# IO_V1_1.net
KiCad netlist of a schematic drawn in EAGLE
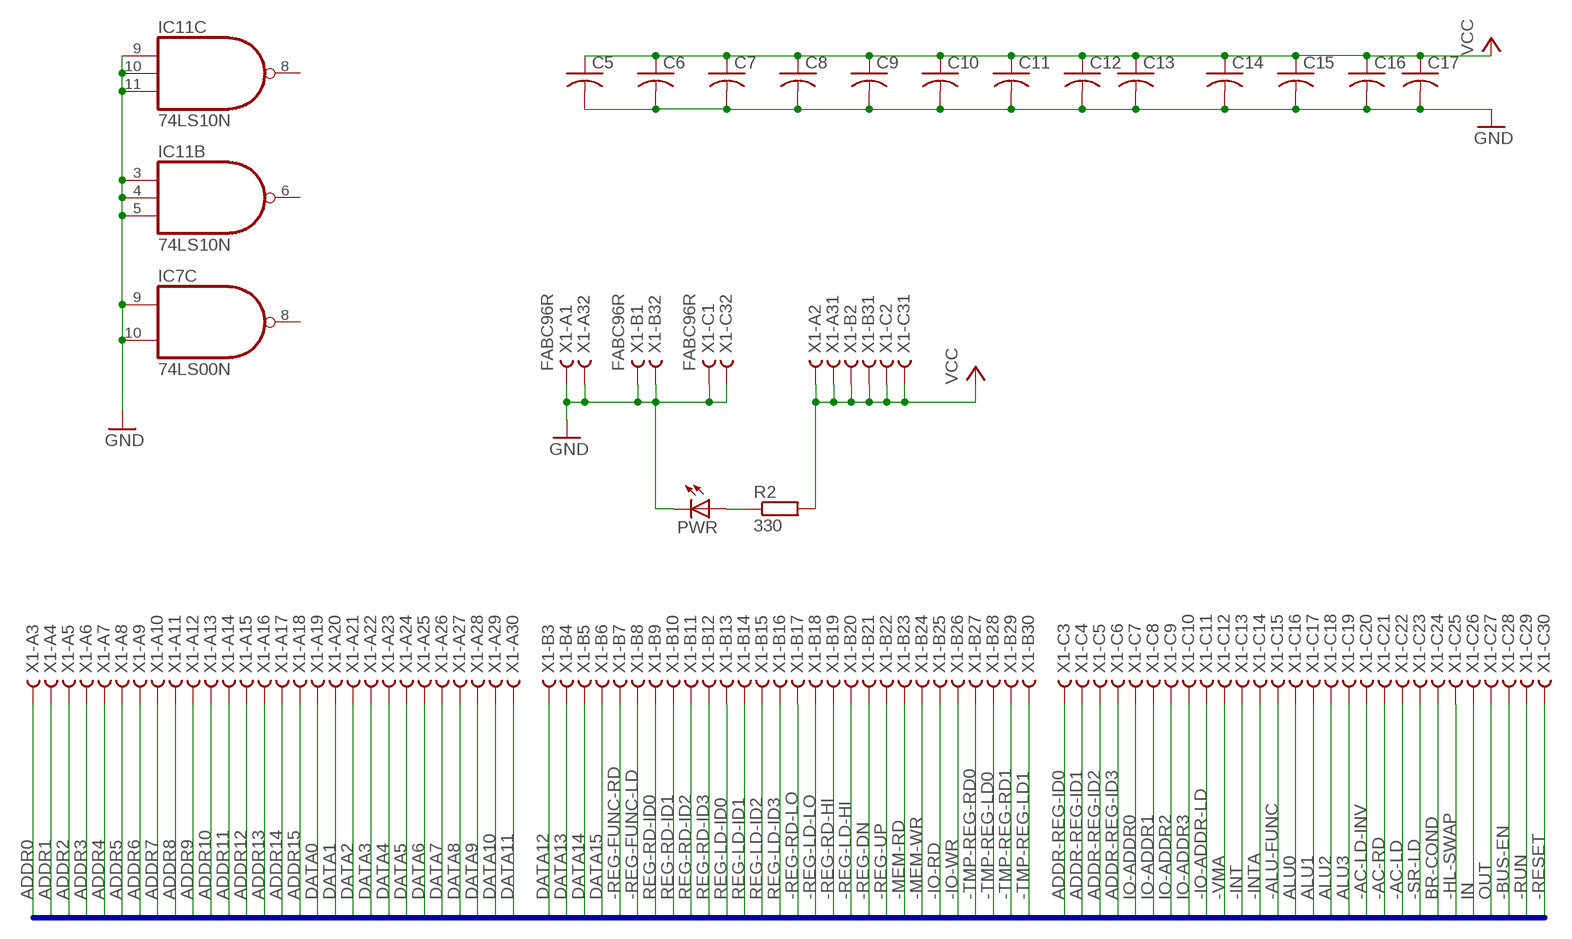
[diagram p0: schematic, sheet 1]
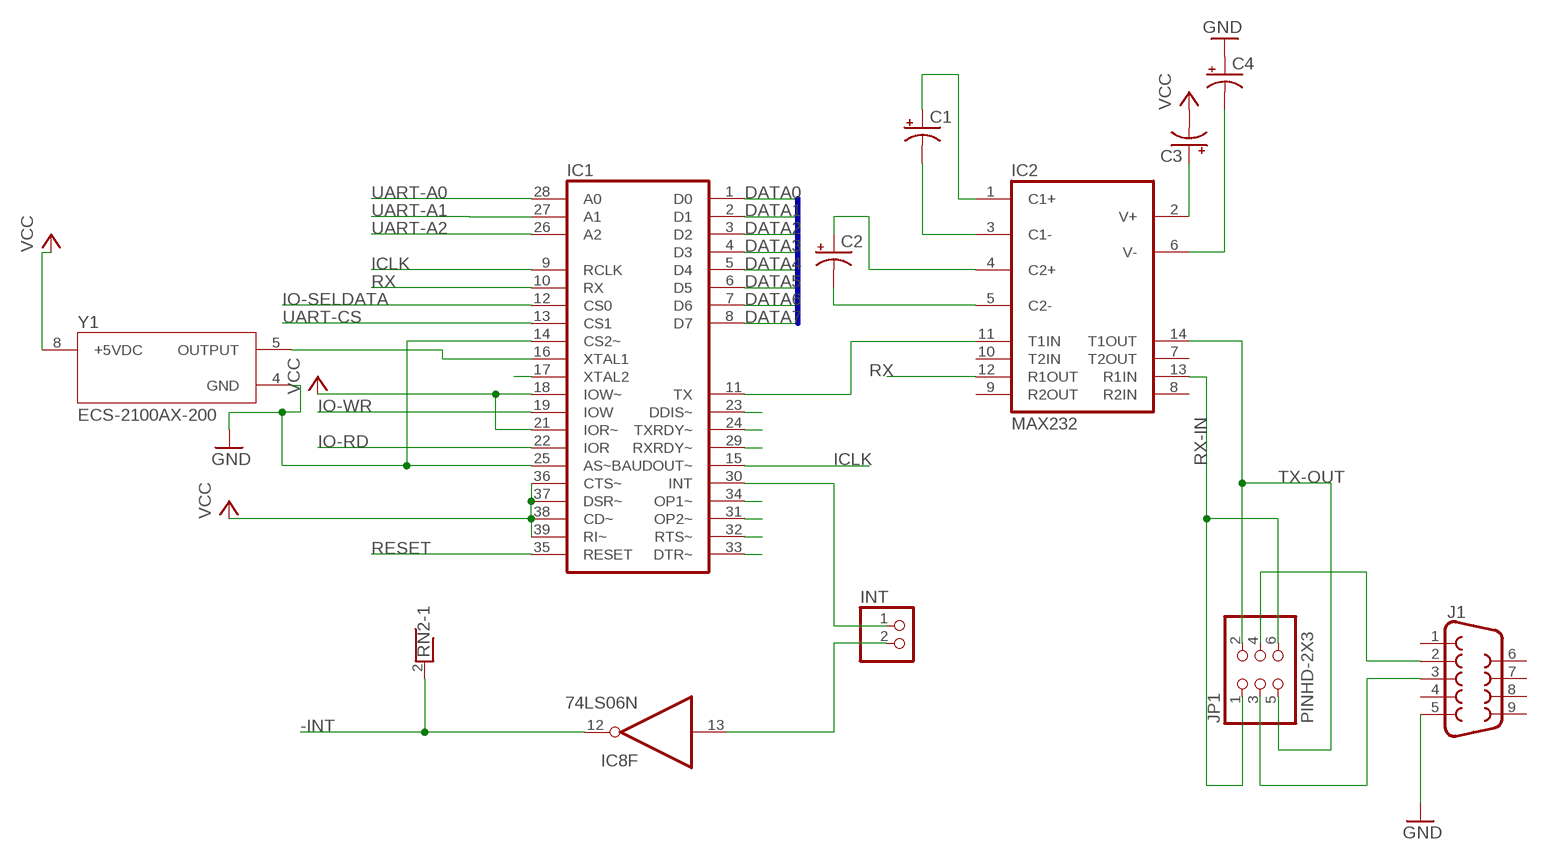
[diagram p1: schematic, sheet 2]
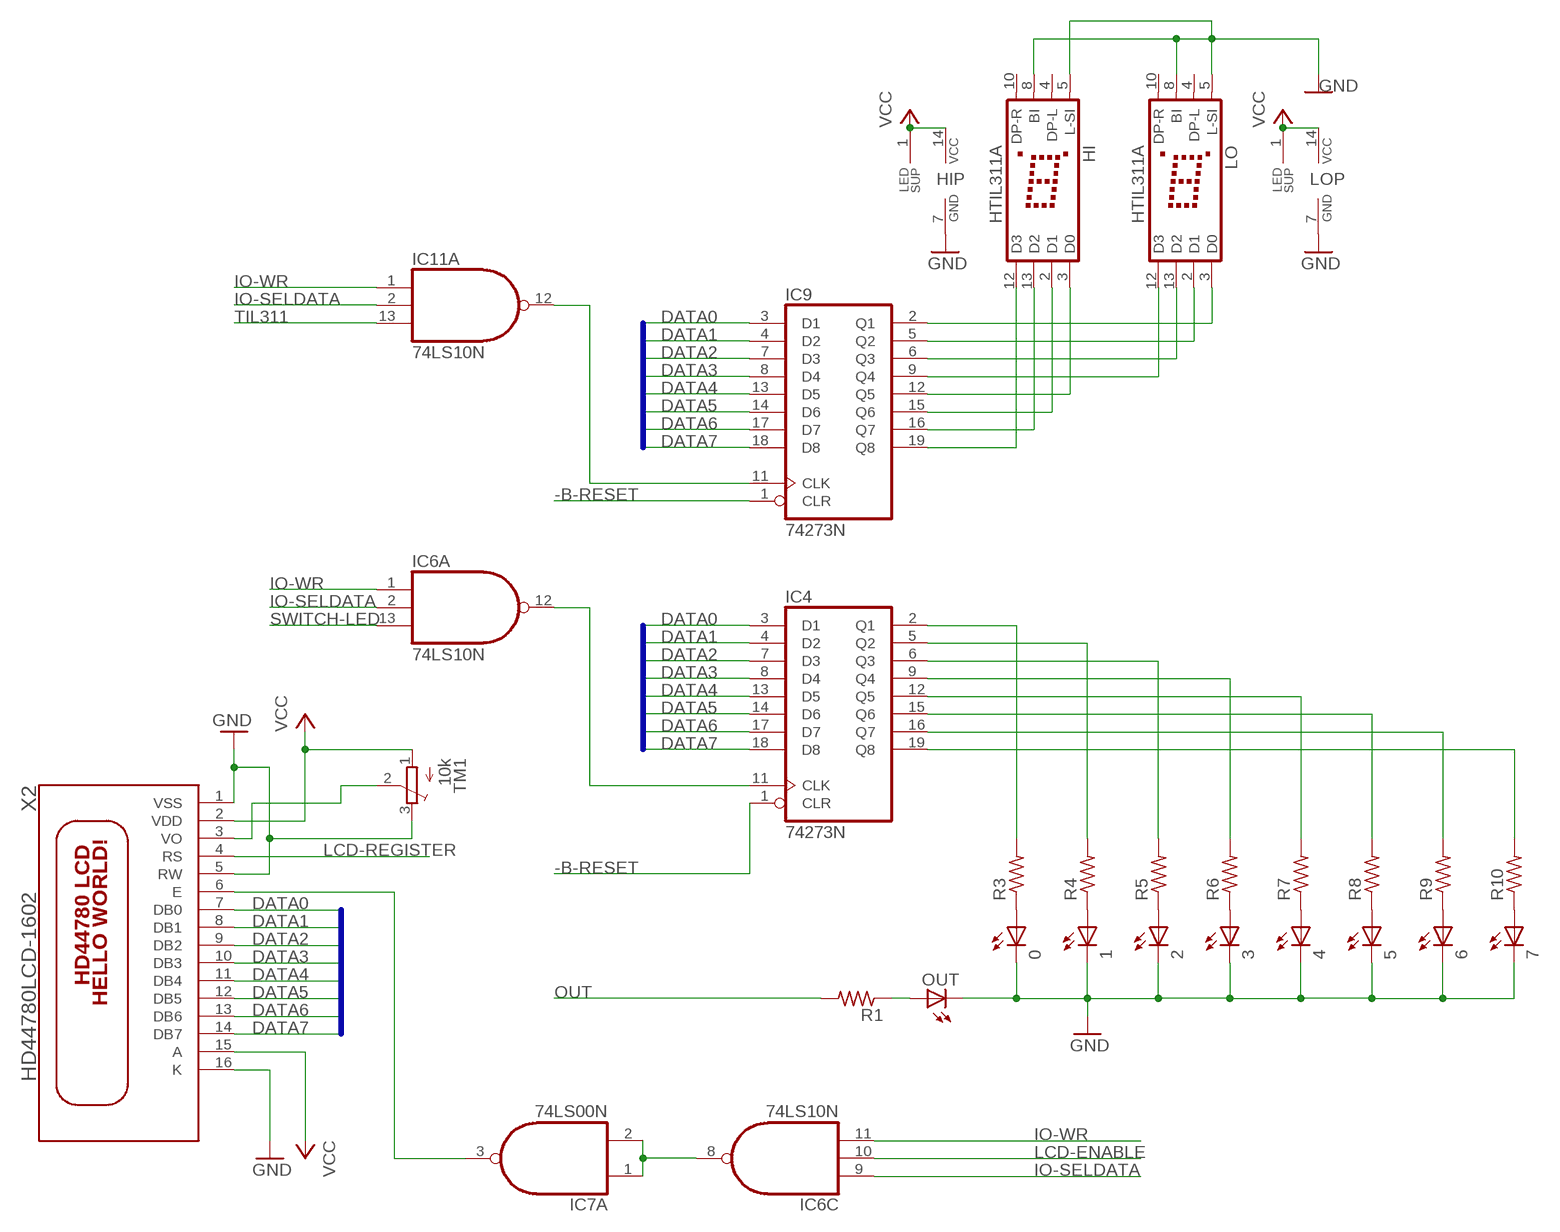
[diagram p2: schematic, sheet 3]
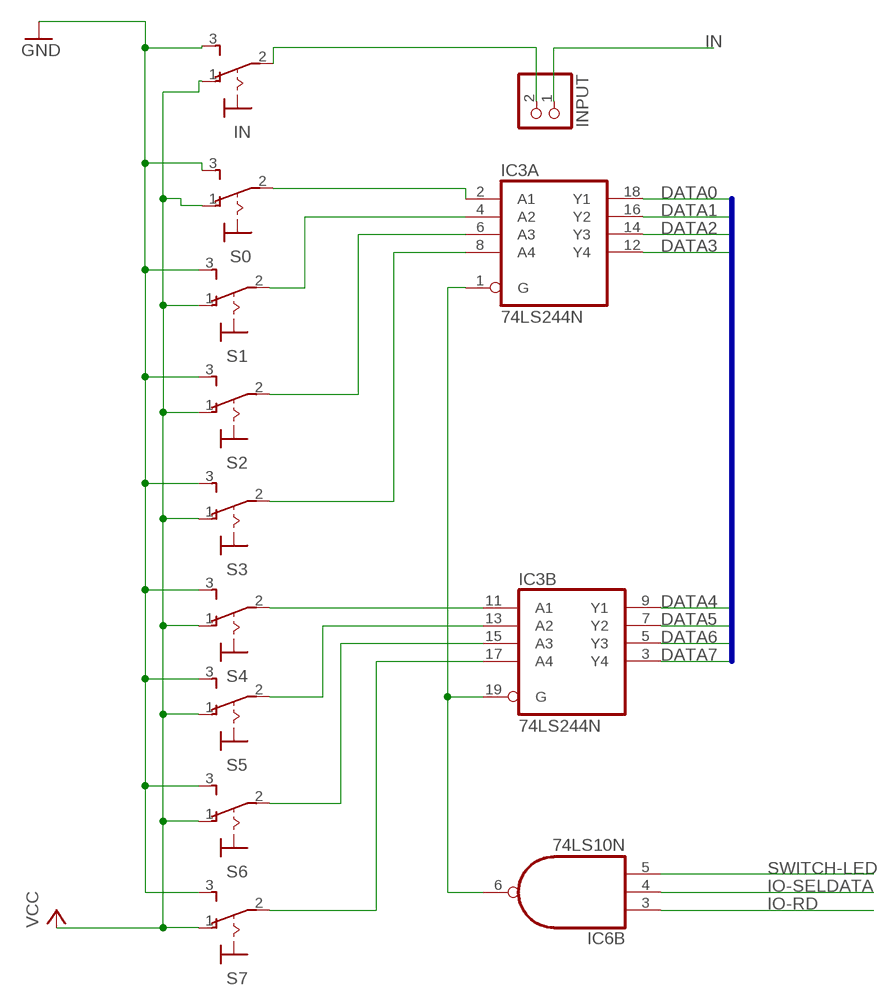
[diagram p3: schematic, sheet 4]
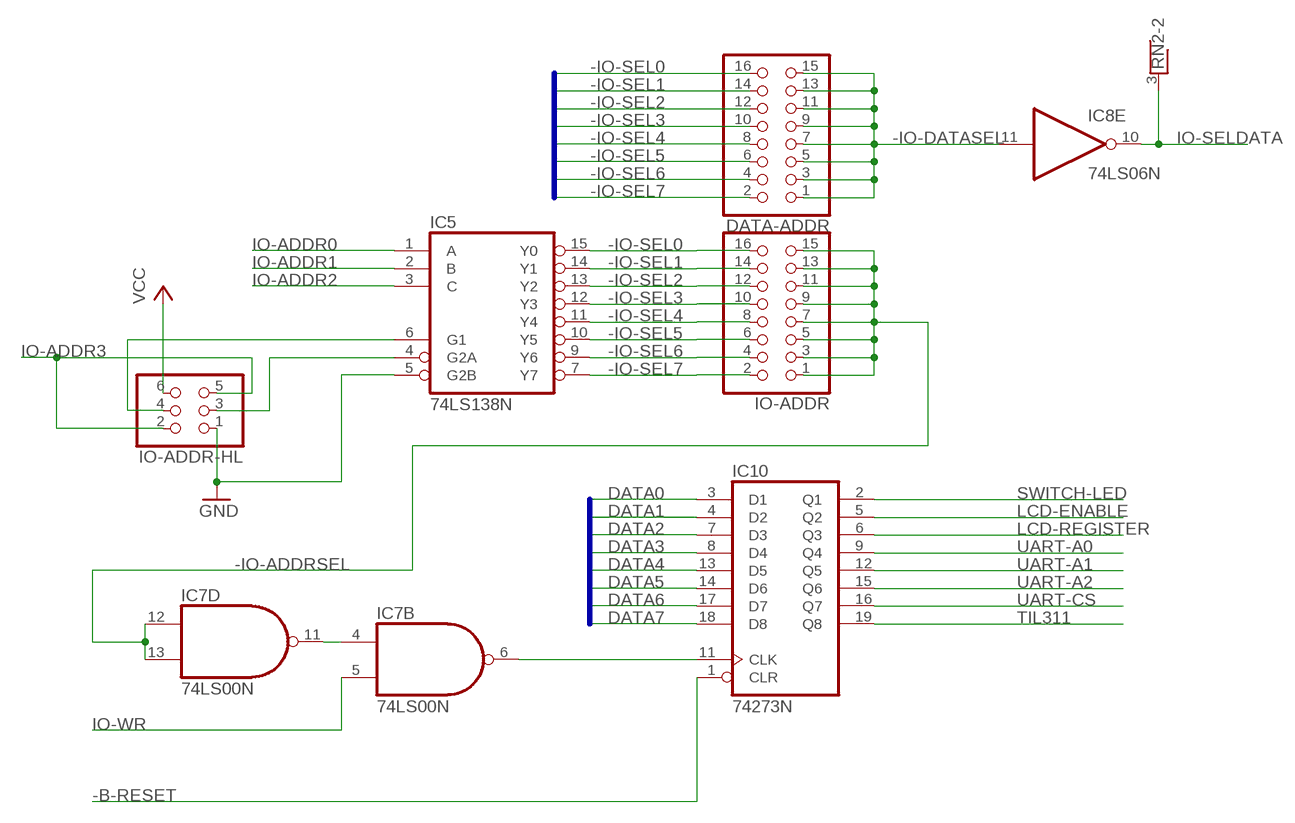
[diagram p4: schematic, sheet 5]
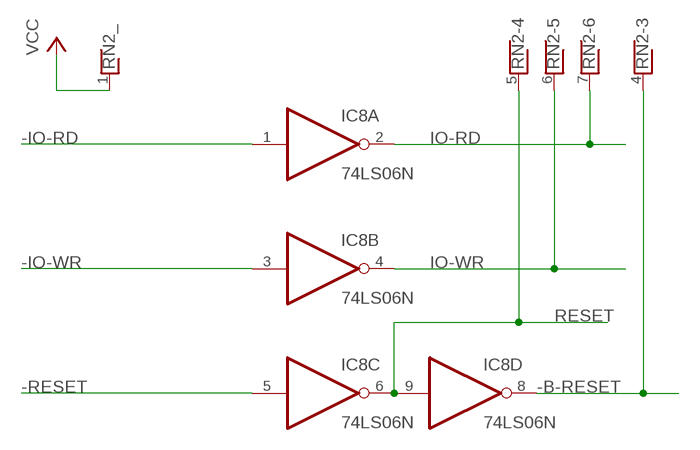
[diagram p5: schematic, sheet 6]

(export (version "E")
  (design (tool "Eeschema 10.0.6"))
  (components
    (comp (ref "DATA-ADDR")
      (value "PINHD-2X8")
      (footprint "eagle-import:2X08")
      (libsource (lib "eagle-import") (part "PINHD-2X8"))
    )
    (comp (ref "IC5")
      (value "74LS138N")
      (footprint "eagle-import:DIL16")
      (libsource (lib "eagle-import") (part "74138NLS"))
    )
    (comp (ref "IC7")
      (value "74LS00N")
      (footprint "eagle-import:DIL14")
      (libsource (lib "eagle-import") (part "7400NLS"))
    )
    (comp (ref "IC8")
      (value "74LS06N")
      (footprint "eagle-import:DIL14")
      (libsource (lib "eagle-import") (part "7406NLS"))
    )
    (comp (ref "IC10")
      (value "74273N")
      (footprint "eagle-import:DIL20")
      (libsource (lib "eagle-import") (part "74273N"))
    )
    (comp (ref "IO-ADDR")
      (value "PINHD-2X8")
      (footprint "eagle-import:2X08")
      (libsource (lib "eagle-import") (part "PINHD-2X8"))
    )
    (comp (ref "IO-ADDR-HL")
      (value "PINHD-2X3")
      (footprint "eagle-import:2X03")
      (libsource (lib "eagle-import") (part "pinhead_325_PINHD-2X3"))
    )
    (comp (ref "RN2")
      (value "RNX6")
      (footprint "eagle-import:RN-7")
      (libsource (lib "eagle-import") (part "RNX6"))
    )
    (comp (ref "C1")
      (value "CPOL-USE2,5-6E")
      (footprint "eagle-import:E2,5-6E")
      (libsource (lib "eagle-import") (part "CPOL-USE2,5-6E"))
    )
    (comp (ref "C2")
      (value "CPOL-USE2,5-6E")
      (footprint "eagle-import:E2,5-6E")
      (libsource (lib "eagle-import") (part "CPOL-USE2,5-6E"))
    )
    (comp (ref "C3")
      (value "CPOL-USE2,5-6E")
      (footprint "eagle-import:E2,5-6E")
      (libsource (lib "eagle-import") (part "CPOL-USE2,5-6E"))
    )
    (comp (ref "C4")
      (value "CPOL-USE2,5-6E")
      (footprint "eagle-import:E2,5-6E")
      (libsource (lib "eagle-import") (part "CPOL-USE2,5-6E"))
    )
    (comp (ref "IC1")
      (value "XR-16C550P")
      (footprint "eagle-import:DIL40")
      (fields (field (name "MPN") "ST16C450CP40"))
      (libsource (lib "eagle-import") (part "XR-16C550P"))
    )
    (comp (ref "IC2")
      (value "MAX232")
      (footprint "eagle-import:DIL16")
      (fields (field (name "MF") "MAXIM") (field (name "MPN") "MAX232ACPE+"))
      (libsource (lib "eagle-import") (part "MAX232"))
    )
    (comp (ref "INT")
      (value "PINHD-1X2")
      (footprint "eagle-import:1X02")
      (libsource (lib "eagle-import") (part "PINHD-1X2"))
    )
    (comp (ref "J1")
      (value "DB9FEMALE")
      (footprint "eagle-import:DB9")
      (libsource (lib "eagle-import") (part "DB9FEMALE"))
    )
    (comp (ref "JP1")
      (value "PINHD-2X3")
      (footprint "eagle-import:2X03")
      (libsource (lib "eagle-import") (part "PINHD-2X3"))
    )
    (comp (ref "Y1")
      (value "ECS-2100AX-200")
      (footprint "eagle-import:ECS-2100AX-200")
      (fields
        (field (name "DIGIKEY_PART_NUMBER") "X964-ND")
        (field (name "MANUFACTURER") "ECS Inc.")
        (field (name "CREATED_BY") "PCBLayout.com")
      )
      (libsource (lib "eagle-import") (part "ECS-2100AX-200"))
    )
    (comp (ref "0")
      (value "LED5MM")
      (footprint "eagle-import:LED5MM")
      (libsource (lib "eagle-import") (part "LED5MM"))
    )
    (comp (ref "1")
      (value "LED5MM")
      (footprint "eagle-import:LED5MM")
      (libsource (lib "eagle-import") (part "LED5MM"))
    )
    (comp (ref "2")
      (value "LED5MM")
      (footprint "eagle-import:LED5MM")
      (libsource (lib "eagle-import") (part "LED5MM"))
    )
    (comp (ref "3")
      (value "LED5MM")
      (footprint "eagle-import:LED5MM")
      (libsource (lib "eagle-import") (part "LED5MM"))
    )
    (comp (ref "4")
      (value "LED5MM")
      (footprint "eagle-import:LED5MM")
      (libsource (lib "eagle-import") (part "LED5MM"))
    )
    (comp (ref "5")
      (value "LED5MM")
      (footprint "eagle-import:LED5MM")
      (libsource (lib "eagle-import") (part "LED5MM"))
    )
    (comp (ref "6")
      (value "LED5MM")
      (footprint "eagle-import:LED5MM")
      (libsource (lib "eagle-import") (part "LED5MM"))
    )
    (comp (ref "7")
      (value "LED5MM")
      (footprint "eagle-import:LED5MM")
      (libsource (lib "eagle-import") (part "LED5MM"))
    )
    (comp (ref "HI")
      (value "HTIL311A")
      (footprint "eagle-import:HTIL311A")
      (libsource (lib "eagle-import") (part "HTIL311A"))
    )
    (comp (ref "IC4")
      (value "74273N")
      (footprint "eagle-import:DIL20")
      (libsource (lib "eagle-import") (part "74273N"))
    )
    (comp (ref "IC6")
      (value "74LS10N")
      (footprint "eagle-import:DIL14")
      (libsource (lib "eagle-import") (part "7410NLS"))
    )
    (comp (ref "IC9")
      (value "74273N")
      (footprint "eagle-import:DIL20")
      (libsource (lib "eagle-import") (part "74273N"))
    )
    (comp (ref "IC11")
      (value "74LS10N")
      (footprint "eagle-import:DIL14")
      (libsource (lib "eagle-import") (part "7410NLS"))
    )
    (comp (ref "LO")
      (value "HTIL311A")
      (footprint "eagle-import:HTIL311A")
      (libsource (lib "eagle-import") (part "HTIL311A"))
    )
    (comp (ref "OUT")
      (value "LED5MM")
      (footprint "eagle-import:LED5MM")
      (libsource (lib "eagle-import") (part "LED5MM"))
    )
    (comp (ref "R1")
      (value "R-US_0207/10")
      (footprint "eagle-import:0207_10")
      (libsource (lib "eagle-import") (part "R-US_0207/10"))
    )
    (comp (ref "R3")
      (value "R-US_0207/10")
      (footprint "eagle-import:0207_10")
      (libsource (lib "eagle-import") (part "R-US_0207/10"))
    )
    (comp (ref "R4")
      (value "R-US_0207/10")
      (footprint "eagle-import:0207_10")
      (libsource (lib "eagle-import") (part "R-US_0207/10"))
    )
    (comp (ref "R5")
      (value "R-US_0207/10")
      (footprint "eagle-import:0207_10")
      (libsource (lib "eagle-import") (part "R-US_0207/10"))
    )
    (comp (ref "R6")
      (value "R-US_0207/10")
      (footprint "eagle-import:0207_10")
      (libsource (lib "eagle-import") (part "R-US_0207/10"))
    )
    (comp (ref "R7")
      (value "R-US_0207/10")
      (footprint "eagle-import:0207_10")
      (libsource (lib "eagle-import") (part "R-US_0207/10"))
    )
    (comp (ref "R8")
      (value "R-US_0207/10")
      (footprint "eagle-import:0207_10")
      (libsource (lib "eagle-import") (part "R-US_0207/10"))
    )
    (comp (ref "R9")
      (value "R-US_0207/10")
      (footprint "eagle-import:0207_10")
      (libsource (lib "eagle-import") (part "R-US_0207/10"))
    )
    (comp (ref "R10")
      (value "R-US_0207/10")
      (footprint "eagle-import:0207_10")
      (libsource (lib "eagle-import") (part "R-US_0207/10"))
    )
    (comp (ref "TM1")
      (value "10k")
      (footprint "eagle-import:TRIM-3386")
      (libsource (lib "eagle-import") (part "TRIMPOT3386"))
    )
    (comp (ref "X2")
      (value "HD44780LCD-1602")
      (footprint "eagle-import:LCD1602")
      (libsource (lib "eagle-import") (part "HD44780LCD-1602"))
    )
    (comp (ref "C5")
      (value "C-US025-024X044")
      (footprint "eagle-import:C025-024X044")
      (libsource (lib "eagle-import") (part "C-US025-024X044"))
    )
    (comp (ref "C6")
      (value "C-US025-024X044")
      (footprint "eagle-import:C025-024X044")
      (libsource (lib "eagle-import") (part "C-US025-024X044"))
    )
    (comp (ref "C7")
      (value "C-US025-024X044")
      (footprint "eagle-import:C025-024X044")
      (libsource (lib "eagle-import") (part "C-US025-024X044"))
    )
    (comp (ref "C8")
      (value "C-US025-024X044")
      (footprint "eagle-import:C025-024X044")
      (libsource (lib "eagle-import") (part "C-US025-024X044"))
    )
    (comp (ref "C9")
      (value "C-US025-024X044")
      (footprint "eagle-import:C025-024X044")
      (libsource (lib "eagle-import") (part "C-US025-024X044"))
    )
    (comp (ref "C10")
      (value "C-US025-024X044")
      (footprint "eagle-import:C025-024X044")
      (libsource (lib "eagle-import") (part "C-US025-024X044"))
    )
    (comp (ref "C11")
      (value "C-US025-024X044")
      (footprint "eagle-import:C025-024X044")
      (libsource (lib "eagle-import") (part "C-US025-024X044"))
    )
    (comp (ref "C12")
      (value "C-US025-024X044")
      (footprint "eagle-import:C025-024X044")
      (libsource (lib "eagle-import") (part "C-US025-024X044"))
    )
    (comp (ref "C13")
      (value "C-US025-024X044")
      (footprint "eagle-import:C025-024X044")
      (libsource (lib "eagle-import") (part "C-US025-024X044"))
    )
    (comp (ref "C14")
      (value "C-US025-024X044")
      (footprint "eagle-import:C025-024X044")
      (libsource (lib "eagle-import") (part "C-US025-024X044"))
    )
    (comp (ref "C15")
      (value "C-US025-024X044")
      (footprint "eagle-import:C025-024X044")
      (libsource (lib "eagle-import") (part "C-US025-024X044"))
    )
    (comp (ref "C16")
      (value "C-US025-024X044")
      (footprint "eagle-import:C025-024X044")
      (libsource (lib "eagle-import") (part "C-US025-024X044"))
    )
    (comp (ref "C17")
      (value "C-US025-024X044")
      (footprint "eagle-import:C025-024X044")
      (libsource (lib "eagle-import") (part "C-US025-024X044"))
    )
    (comp (ref "PWR")
      (value "LED5MM")
      (footprint "eagle-import:LED5MM")
      (libsource (lib "eagle-import") (part "led_LED5MM"))
    )
    (comp (ref "R2")
      (value "330")
      (footprint "eagle-import:0207_10")
      (libsource (lib "eagle-import") (part "R0207/10"))
    )
    (comp (ref "X1")
      (value "FABC96R")
      (footprint "eagle-import:FABC96R")
      (libsource (lib "eagle-import") (part "FABC96R"))
    )
    (comp (ref "IC3")
      (value "74LS244N")
      (footprint "eagle-import:DIL20")
      (libsource (lib "eagle-import") (part "74xx-us_88_74244NLS"))
    )
    (comp (ref "IN")
      (value "M9040P")
      (footprint "eagle-import:M9040P")
      (libsource (lib "eagle-import") (part "M9040P"))
    )
    (comp (ref "INPUT")
      (value "PINHD-1X2")
      (footprint "eagle-import:1X02")
      (libsource (lib "eagle-import") (part "PINHD-1X2"))
    )
    (comp (ref "S0")
      (value "M9040P")
      (footprint "eagle-import:M9040P")
      (libsource (lib "eagle-import") (part "M9040P"))
    )
    (comp (ref "S1")
      (value "M9040P")
      (footprint "eagle-import:M9040P")
      (libsource (lib "eagle-import") (part "M9040P"))
    )
    (comp (ref "S2")
      (value "M9040P")
      (footprint "eagle-import:M9040P")
      (libsource (lib "eagle-import") (part "M9040P"))
    )
    (comp (ref "S3")
      (value "M9040P")
      (footprint "eagle-import:M9040P")
      (libsource (lib "eagle-import") (part "M9040P"))
    )
    (comp (ref "S4")
      (value "M9040P")
      (footprint "eagle-import:M9040P")
      (libsource (lib "eagle-import") (part "M9040P"))
    )
    (comp (ref "S5")
      (value "M9040P")
      (footprint "eagle-import:M9040P")
      (libsource (lib "eagle-import") (part "M9040P"))
    )
    (comp (ref "S6")
      (value "M9040P")
      (footprint "eagle-import:M9040P")
      (libsource (lib "eagle-import") (part "M9040P"))
    )
    (comp (ref "S7")
      (value "M9040P")
      (footprint "eagle-import:M9040P")
      (libsource (lib "eagle-import") (part "M9040P"))
    )
  )
  (nets
    (net (code "1") (name "-AC-LD") (class "Default")
      (node (ref "X1") (pin "C22") (pinfunction "B_C22") (pintype "passive"))
    )
    (net (code "2") (name "-AC-LD-INV") (class "Default")
      (node (ref "X1") (pin "C20") (pinfunction "B_C20") (pintype "passive"))
    )
    (net (code "3") (name "-AC-RD") (class "Default")
      (node (ref "X1") (pin "C21") (pinfunction "B_C21") (pintype "passive"))
    )
    (net (code "4") (name "-ALU-FUNC") (class "Default")
      (node (ref "X1") (pin "C15") (pinfunction "B_C15") (pintype "passive"))
    )
    (net (code "5") (name "-B-RESET") (class "Default")
      (node (ref "IC10") (pin "1") (pinfunction "CLR_1") (pintype "input"))
      (node (ref "IC4") (pin "1") (pinfunction "CLR_1") (pintype "input"))
      (node (ref "IC8") (pin "8") (pinfunction "O_8") (pintype "open_collector"))
      (node (ref "IC9") (pin "1") (pinfunction "CLR_1") (pintype "input"))
      (node (ref "RN2") (pin "4") (pinfunction "1_4") (pintype "passive"))
    )
    (net (code "6") (name "-BUS-EN") (class "Default")
      (node (ref "X1") (pin "C28") (pinfunction "B_C28") (pintype "passive"))
    )
    (net (code "7") (name "-HL-SWAP") (class "Default")
      (node (ref "X1") (pin "C25") (pinfunction "B_C25") (pintype "passive"))
    )
    (net (code "8") (name "-INT") (class "Default")
      (node (ref "IC8") (pin "12") (pinfunction "O_12") (pintype "open_collector"))
      (node (ref "RN2") (pin "2") (pinfunction "1_2") (pintype "passive"))
      (node (ref "X1") (pin "C13") (pinfunction "B_C13") (pintype "passive"))
    )
    (net (code "9") (name "-INTA") (class "Default")
      (node (ref "X1") (pin "C14") (pinfunction "B_C14") (pintype "passive"))
    )
    (net (code "10") (name "-IO-ADDR-LD") (class "Default")
      (node (ref "X1") (pin "C11") (pinfunction "B_C11") (pintype "passive"))
    )
    (net (code "11") (name "-IO-ADDRSEL") (class "Default")
      (node (ref "IC7") (pin "12") (pinfunction "I0_12") (pintype "input"))
      (node (ref "IC7") (pin "13") (pinfunction "I1_13") (pintype "input"))
      (node (ref "IO-ADDR") (pin "1") (pinfunction "1_1") (pintype "passive"))
      (node (ref "IO-ADDR") (pin "11") (pinfunction "11_11") (pintype "passive"))
      (node (ref "IO-ADDR") (pin "13") (pinfunction "13_13") (pintype "passive"))
      (node (ref "IO-ADDR") (pin "15") (pinfunction "15_15") (pintype "passive"))
      (node (ref "IO-ADDR") (pin "3") (pinfunction "3_3") (pintype "passive"))
      (node (ref "IO-ADDR") (pin "5") (pinfunction "5_5") (pintype "passive"))
      (node (ref "IO-ADDR") (pin "7") (pinfunction "7_7") (pintype "passive"))
      (node (ref "IO-ADDR") (pin "9") (pinfunction "9_9") (pintype "passive"))
    )
    (net (code "12") (name "-IO-DATASEL") (class "Default")
      (node (ref "DATA-ADDR") (pin "1") (pinfunction "1_1") (pintype "passive"))
      (node (ref "DATA-ADDR") (pin "11") (pinfunction "11_11") (pintype "passive"))
      (node (ref "DATA-ADDR") (pin "13") (pinfunction "13_13") (pintype "passive"))
      (node (ref "DATA-ADDR") (pin "15") (pinfunction "15_15") (pintype "passive"))
      (node (ref "DATA-ADDR") (pin "3") (pinfunction "3_3") (pintype "passive"))
      (node (ref "DATA-ADDR") (pin "5") (pinfunction "5_5") (pintype "passive"))
      (node (ref "DATA-ADDR") (pin "7") (pinfunction "7_7") (pintype "passive"))
      (node (ref "DATA-ADDR") (pin "9") (pinfunction "9_9") (pintype "passive"))
      (node (ref "IC8") (pin "11") (pinfunction "I_11") (pintype "input"))
    )
    (net (code "13") (name "-IO-RD") (class "Default")
      (node (ref "IC8") (pin "1") (pinfunction "I_1") (pintype "input"))
      (node (ref "X1") (pin "B25") (pinfunction "B_B25") (pintype "passive"))
    )
    (net (code "14") (name "-IO-SEL0") (class "Default")
      (node (ref "DATA-ADDR") (pin "16") (pinfunction "16_16") (pintype "passive"))
      (node (ref "IC5") (pin "15") (pinfunction "Y0_15") (pintype "output"))
      (node (ref "IO-ADDR") (pin "16") (pinfunction "16_16") (pintype "passive"))
    )
    (net (code "15") (name "-IO-SEL1") (class "Default")
      (node (ref "DATA-ADDR") (pin "14") (pinfunction "14_14") (pintype "passive"))
      (node (ref "IC5") (pin "14") (pinfunction "Y1_14") (pintype "output"))
      (node (ref "IO-ADDR") (pin "14") (pinfunction "14_14") (pintype "passive"))
    )
    (net (code "16") (name "-IO-SEL2") (class "Default")
      (node (ref "DATA-ADDR") (pin "12") (pinfunction "12_12") (pintype "passive"))
      (node (ref "IC5") (pin "13") (pinfunction "Y2_13") (pintype "output"))
      (node (ref "IO-ADDR") (pin "12") (pinfunction "12_12") (pintype "passive"))
    )
    (net (code "17") (name "-IO-SEL3") (class "Default")
      (node (ref "DATA-ADDR") (pin "10") (pinfunction "10_10") (pintype "passive"))
      (node (ref "IC5") (pin "12") (pinfunction "Y3_12") (pintype "output"))
      (node (ref "IO-ADDR") (pin "10") (pinfunction "10_10") (pintype "passive"))
    )
    (net (code "18") (name "-IO-SEL4") (class "Default")
      (node (ref "DATA-ADDR") (pin "8") (pinfunction "8_8") (pintype "passive"))
      (node (ref "IC5") (pin "11") (pinfunction "Y4_11") (pintype "output"))
      (node (ref "IO-ADDR") (pin "8") (pinfunction "8_8") (pintype "passive"))
    )
    (net (code "19") (name "-IO-SEL5") (class "Default")
      (node (ref "DATA-ADDR") (pin "6") (pinfunction "6_6") (pintype "passive"))
      (node (ref "IC5") (pin "10") (pinfunction "Y5_10") (pintype "output"))
      (node (ref "IO-ADDR") (pin "6") (pinfunction "6_6") (pintype "passive"))
    )
    (net (code "20") (name "-IO-SEL6") (class "Default")
      (node (ref "DATA-ADDR") (pin "4") (pinfunction "4_4") (pintype "passive"))
      (node (ref "IC5") (pin "9") (pinfunction "Y6_9") (pintype "output"))
      (node (ref "IO-ADDR") (pin "4") (pinfunction "4_4") (pintype "passive"))
    )
    (net (code "21") (name "-IO-SEL7") (class "Default")
      (node (ref "DATA-ADDR") (pin "2") (pinfunction "2_2") (pintype "passive"))
      (node (ref "IC5") (pin "7") (pinfunction "Y7_7") (pintype "output"))
      (node (ref "IO-ADDR") (pin "2") (pinfunction "2_2") (pintype "passive"))
    )
    (net (code "22") (name "-IO-WR") (class "Default")
      (node (ref "IC8") (pin "3") (pinfunction "I_3") (pintype "input"))
      (node (ref "X1") (pin "B26") (pinfunction "B_B26") (pintype "passive"))
    )
    (net (code "23") (name "-MEM-RD") (class "Default")
      (node (ref "X1") (pin "B23") (pinfunction "B_B23") (pintype "passive"))
    )
    (net (code "24") (name "-MEM-WR") (class "Default")
      (node (ref "X1") (pin "B24") (pinfunction "B_B24") (pintype "passive"))
    )
    (net (code "25") (name "-REG-DN") (class "Default")
      (node (ref "X1") (pin "B21") (pinfunction "B_B21") (pintype "passive"))
    )
    (net (code "26") (name "-REG-FUNC-LD") (class "Default")
      (node (ref "X1") (pin "B8") (pinfunction "B_B8") (pintype "passive"))
    )
    (net (code "27") (name "-REG-FUNC-RD") (class "Default")
      (node (ref "X1") (pin "B7") (pinfunction "B_B7") (pintype "passive"))
    )
    (net (code "28") (name "-REG-LD-HI") (class "Default")
      (node (ref "X1") (pin "B20") (pinfunction "B_B20") (pintype "passive"))
    )
    (net (code "29") (name "-REG-LD-LO") (class "Default")
      (node (ref "X1") (pin "B18") (pinfunction "B_B18") (pintype "passive"))
    )
    (net (code "30") (name "-REG-RD-HI") (class "Default")
      (node (ref "X1") (pin "B19") (pinfunction "B_B19") (pintype "passive"))
    )
    (net (code "31") (name "-REG-RD-LO") (class "Default")
      (node (ref "X1") (pin "B17") (pinfunction "B_B17") (pintype "passive"))
    )
    (net (code "32") (name "-REG-UP") (class "Default")
      (node (ref "X1") (pin "B22") (pinfunction "B_B22") (pintype "passive"))
    )
    (net (code "33") (name "-RESET") (class "Default")
      (node (ref "IC8") (pin "5") (pinfunction "I_5") (pintype "input"))
      (node (ref "X1") (pin "C30") (pinfunction "B_C30") (pintype "passive"))
    )
    (net (code "34") (name "-RUN") (class "Default")
      (node (ref "X1") (pin "C29") (pinfunction "B_C29") (pintype "passive"))
    )
    (net (code "35") (name "-SR-LD") (class "Default")
      (node (ref "X1") (pin "C23") (pinfunction "B_C23") (pintype "passive"))
    )
    (net (code "36") (name "-TMP-REG-LD0") (class "Default")
      (node (ref "X1") (pin "B28") (pinfunction "B_B28") (pintype "passive"))
    )
    (net (code "37") (name "-TMP-REG-LD1") (class "Default")
      (node (ref "X1") (pin "B30") (pinfunction "B_B30") (pintype "passive"))
    )
    (net (code "38") (name "-TMP-REG-RD0") (class "Default")
      (node (ref "X1") (pin "B27") (pinfunction "B_B27") (pintype "passive"))
    )
    (net (code "39") (name "-TMP-REG-RD1") (class "Default")
      (node (ref "X1") (pin "B29") (pinfunction "B_B29") (pintype "passive"))
    )
    (net (code "40") (name "-VMA") (class "Default")
      (node (ref "X1") (pin "C12") (pinfunction "B_C12") (pintype "passive"))
    )
    (net (code "41") (name "ADDR-REG-ID0") (class "Default")
      (node (ref "X1") (pin "C3") (pinfunction "B_C3") (pintype "passive"))
    )
    (net (code "42") (name "ADDR-REG-ID1") (class "Default")
      (node (ref "X1") (pin "C4") (pinfunction "B_C4") (pintype "passive"))
    )
    (net (code "43") (name "ADDR-REG-ID2") (class "Default")
      (node (ref "X1") (pin "C5") (pinfunction "B_C5") (pintype "passive"))
    )
    (net (code "44") (name "ADDR-REG-ID3") (class "Default")
      (node (ref "X1") (pin "C6") (pinfunction "B_C6") (pintype "passive"))
    )
    (net (code "45") (name "ADDR0") (class "Default")
      (node (ref "X1") (pin "A3") (pinfunction "B_A3") (pintype "passive"))
    )
    (net (code "46") (name "ADDR1") (class "Default")
      (node (ref "X1") (pin "A4") (pinfunction "B_A4") (pintype "passive"))
    )
    (net (code "47") (name "ADDR2") (class "Default")
      (node (ref "X1") (pin "A5") (pinfunction "B_A5") (pintype "passive"))
    )
    (net (code "48") (name "ADDR3") (class "Default")
      (node (ref "X1") (pin "A6") (pinfunction "B_A6") (pintype "passive"))
    )
    (net (code "49") (name "ADDR4") (class "Default")
      (node (ref "X1") (pin "A7") (pinfunction "B_A7") (pintype "passive"))
    )
    (net (code "50") (name "ADDR5") (class "Default")
      (node (ref "X1") (pin "A8") (pinfunction "B_A8") (pintype "passive"))
    )
    (net (code "51") (name "ADDR6") (class "Default")
      (node (ref "X1") (pin "A9") (pinfunction "B_A9") (pintype "passive"))
    )
    (net (code "52") (name "ADDR7") (class "Default")
      (node (ref "X1") (pin "A10") (pinfunction "B_A10") (pintype "passive"))
    )
    (net (code "53") (name "ADDR8") (class "Default")
      (node (ref "X1") (pin "A11") (pinfunction "B_A11") (pintype "passive"))
    )
    (net (code "54") (name "ADDR9") (class "Default")
      (node (ref "X1") (pin "A12") (pinfunction "B_A12") (pintype "passive"))
    )
    (net (code "55") (name "ADDR10") (class "Default")
      (node (ref "X1") (pin "A13") (pinfunction "B_A13") (pintype "passive"))
    )
    (net (code "56") (name "ADDR11") (class "Default")
      (node (ref "X1") (pin "A14") (pinfunction "B_A14") (pintype "passive"))
    )
    (net (code "57") (name "ADDR12") (class "Default")
      (node (ref "X1") (pin "A15") (pinfunction "B_A15") (pintype "passive"))
    )
    (net (code "58") (name "ADDR13") (class "Default")
      (node (ref "X1") (pin "A16") (pinfunction "B_A16") (pintype "passive"))
    )
    (net (code "59") (name "ADDR14") (class "Default")
      (node (ref "X1") (pin "A17") (pinfunction "B_A17") (pintype "passive"))
    )
    (net (code "60") (name "ADDR15") (class "Default")
      (node (ref "X1") (pin "A18") (pinfunction "B_A18") (pintype "passive"))
    )
    (net (code "61") (name "ALU0") (class "Default")
      (node (ref "X1") (pin "C16") (pinfunction "B_C16") (pintype "passive"))
    )
    (net (code "62") (name "ALU1") (class "Default")
      (node (ref "X1") (pin "C17") (pinfunction "B_C17") (pintype "passive"))
    )
    (net (code "63") (name "ALU2") (class "Default")
      (node (ref "X1") (pin "C18") (pinfunction "B_C18") (pintype "passive"))
    )
    (net (code "64") (name "ALU3") (class "Default")
      (node (ref "X1") (pin "C19") (pinfunction "B_C19") (pintype "passive"))
    )
    (net (code "65") (name "BR-COND") (class "Default")
      (node (ref "X1") (pin "C24") (pinfunction "B_C24") (pintype "passive"))
    )
    (net (code "66") (name "DATA0") (class "Default")
      (node (ref "IC1") (pin "1") (pinfunction "D0_1") (pintype "bidirectional"))
      (node (ref "IC10") (pin "3") (pinfunction "D1_3") (pintype "input"))
      (node (ref "IC3") (pin "18") (pinfunction "Y1_18") (pintype "tri_state"))
      (node (ref "IC4") (pin "3") (pinfunction "D1_3") (pintype "input"))
      (node (ref "IC9") (pin "3") (pinfunction "D1_3") (pintype "input"))
      (node (ref "X1") (pin "A19") (pinfunction "B_A19") (pintype "passive"))
      (node (ref "X2") (pin "7") (pinfunction "DB0_7") (pintype "bidirectional"))
    )
    (net (code "67") (name "DATA1") (class "Default")
      (node (ref "IC1") (pin "2") (pinfunction "D1_2") (pintype "bidirectional"))
      (node (ref "IC10") (pin "4") (pinfunction "D2_4") (pintype "input"))
      (node (ref "IC3") (pin "16") (pinfunction "Y2_16") (pintype "tri_state"))
      (node (ref "IC4") (pin "4") (pinfunction "D2_4") (pintype "input"))
      (node (ref "IC9") (pin "4") (pinfunction "D2_4") (pintype "input"))
      (node (ref "X1") (pin "A20") (pinfunction "B_A20") (pintype "passive"))
      (node (ref "X2") (pin "8") (pinfunction "DB1_8") (pintype "bidirectional"))
    )
    (net (code "68") (name "DATA2") (class "Default")
      (node (ref "IC1") (pin "3") (pinfunction "D2_3") (pintype "bidirectional"))
      (node (ref "IC10") (pin "7") (pinfunction "D3_7") (pintype "input"))
      (node (ref "IC3") (pin "14") (pinfunction "Y3_14") (pintype "tri_state"))
      (node (ref "IC4") (pin "7") (pinfunction "D3_7") (pintype "input"))
      (node (ref "IC9") (pin "7") (pinfunction "D3_7") (pintype "input"))
      (node (ref "X1") (pin "A21") (pinfunction "B_A21") (pintype "passive"))
      (node (ref "X2") (pin "9") (pinfunction "DB2_9") (pintype "bidirectional"))
    )
    (net (code "69") (name "DATA3") (class "Default")
      (node (ref "IC1") (pin "4") (pinfunction "D3_4") (pintype "bidirectional"))
      (node (ref "IC10") (pin "8") (pinfunction "D4_8") (pintype "input"))
      (node (ref "IC3") (pin "12") (pinfunction "Y4_12") (pintype "tri_state"))
      (node (ref "IC4") (pin "8") (pinfunction "D4_8") (pintype "input"))
      (node (ref "IC9") (pin "8") (pinfunction "D4_8") (pintype "input"))
      (node (ref "X1") (pin "A22") (pinfunction "B_A22") (pintype "passive"))
      (node (ref "X2") (pin "10") (pinfunction "DB3_10") (pintype "bidirectional"))
    )
    (net (code "70") (name "DATA4") (class "Default")
      (node (ref "IC1") (pin "5") (pinfunction "D4_5") (pintype "bidirectional"))
      (node (ref "IC10") (pin "13") (pinfunction "D5_13") (pintype "input"))
      (node (ref "IC3") (pin "9") (pinfunction "Y1_9") (pintype "tri_state"))
      (node (ref "IC4") (pin "13") (pinfunction "D5_13") (pintype "input"))
      (node (ref "IC9") (pin "13") (pinfunction "D5_13") (pintype "input"))
      (node (ref "X1") (pin "A23") (pinfunction "B_A23") (pintype "passive"))
      (node (ref "X2") (pin "11") (pinfunction "DB4_11") (pintype "bidirectional"))
    )
    (net (code "71") (name "DATA5") (class "Default")
      (node (ref "IC1") (pin "6") (pinfunction "D5_6") (pintype "bidirectional"))
      (node (ref "IC10") (pin "14") (pinfunction "D6_14") (pintype "input"))
      (node (ref "IC3") (pin "7") (pinfunction "Y2_7") (pintype "tri_state"))
      (node (ref "IC4") (pin "14") (pinfunction "D6_14") (pintype "input"))
      (node (ref "IC9") (pin "14") (pinfunction "D6_14") (pintype "input"))
      (node (ref "X1") (pin "A24") (pinfunction "B_A24") (pintype "passive"))
      (node (ref "X2") (pin "12") (pinfunction "DB5_12") (pintype "bidirectional"))
    )
    (net (code "72") (name "DATA6") (class "Default")
      (node (ref "IC1") (pin "7") (pinfunction "D6_7") (pintype "bidirectional"))
      (node (ref "IC10") (pin "17") (pinfunction "D7_17") (pintype "input"))
      (node (ref "IC3") (pin "5") (pinfunction "Y3_5") (pintype "tri_state"))
      (node (ref "IC4") (pin "17") (pinfunction "D7_17") (pintype "input"))
      (node (ref "IC9") (pin "17") (pinfunction "D7_17") (pintype "input"))
      (node (ref "X1") (pin "A25") (pinfunction "B_A25") (pintype "passive"))
      (node (ref "X2") (pin "13") (pinfunction "DB6_13") (pintype "bidirectional"))
    )
    (net (code "73") (name "DATA7") (class "Default")
      (node (ref "IC1") (pin "8") (pinfunction "D7_8") (pintype "bidirectional"))
      (node (ref "IC10") (pin "18") (pinfunction "D8_18") (pintype "input"))
      (node (ref "IC3") (pin "3") (pinfunction "Y4_3") (pintype "tri_state"))
      (node (ref "IC4") (pin "18") (pinfunction "D8_18") (pintype "input"))
      (node (ref "IC9") (pin "18") (pinfunction "D8_18") (pintype "input"))
      (node (ref "X1") (pin "A26") (pinfunction "B_A26") (pintype "passive"))
      (node (ref "X2") (pin "14") (pinfunction "DB7_14") (pintype "bidirectional"))
    )
    (net (code "74") (name "DATA8") (class "Default")
      (node (ref "X1") (pin "A27") (pinfunction "B_A27") (pintype "passive"))
    )
    (net (code "75") (name "DATA9") (class "Default")
      (node (ref "X1") (pin "A28") (pinfunction "B_A28") (pintype "passive"))
    )
    (net (code "76") (name "DATA10") (class "Default")
      (node (ref "X1") (pin "A29") (pinfunction "B_A29") (pintype "passive"))
    )
    (net (code "77") (name "DATA11") (class "Default")
      (node (ref "X1") (pin "A30") (pinfunction "B_A30") (pintype "passive"))
    )
    (net (code "78") (name "DATA12") (class "Default")
      (node (ref "X1") (pin "B3") (pinfunction "B_B3") (pintype "passive"))
    )
    (net (code "79") (name "DATA13") (class "Default")
      (node (ref "X1") (pin "B4") (pinfunction "B_B4") (pintype "passive"))
    )
    (net (code "80") (name "DATA14") (class "Default")
      (node (ref "X1") (pin "B5") (pinfunction "B_B5") (pintype "passive"))
    )
    (net (code "81") (name "DATA15") (class "Default")
      (node (ref "X1") (pin "B6") (pinfunction "B_B6") (pintype "passive"))
    )
    (net (code "82") (name "GND") (class "Default")
      (node (ref "0") (pin "K") (pinfunction "C_K") (pintype "passive"))
      (node (ref "1") (pin "K") (pinfunction "C_K") (pintype "passive"))
      (node (ref "2") (pin "K") (pinfunction "C_K") (pintype "passive"))
      (node (ref "3") (pin "K") (pinfunction "C_K") (pintype "passive"))
      (node (ref "4") (pin "K") (pinfunction "C_K") (pintype "passive"))
      (node (ref "5") (pin "K") (pinfunction "C_K") (pintype "passive"))
      (node (ref "6") (pin "K") (pinfunction "C_K") (pintype "passive"))
      (node (ref "7") (pin "K") (pinfunction "C_K") (pintype "passive"))
      (node (ref "C10") (pin "2") (pinfunction "2_2") (pintype "passive"))
      (node (ref "C11") (pin "2") (pinfunction "2_2") (pintype "passive"))
      (node (ref "C12") (pin "2") (pinfunction "2_2") (pintype "passive"))
      (node (ref "C13") (pin "2") (pinfunction "2_2") (pintype "passive"))
      (node (ref "C14") (pin "2") (pinfunction "2_2") (pintype "passive"))
      (node (ref "C15") (pin "2") (pinfunction "2_2") (pintype "passive"))
      (node (ref "C16") (pin "2") (pinfunction "2_2") (pintype "passive"))
      (node (ref "C17") (pin "2") (pinfunction "2_2") (pintype "passive"))
      (node (ref "C4") (pin "+") (pinfunction "+_+") (pintype "passive"))
      (node (ref "C5") (pin "2") (pinfunction "2_2") (pintype "passive"))
      (node (ref "C6") (pin "2") (pinfunction "2_2") (pintype "passive"))
      (node (ref "C7") (pin "2") (pinfunction "2_2") (pintype "passive"))
      (node (ref "C8") (pin "2") (pinfunction "2_2") (pintype "passive"))
      (node (ref "C9") (pin "2") (pinfunction "2_2") (pintype "passive"))
      (node (ref "HI") (pin "5") (pinfunction "L-SI_5") (pintype "input"))
      (node (ref "HI") (pin "7") (pinfunction "GND_7") (pintype "power_in"))
      (node (ref "HI") (pin "8") (pinfunction "BI_8") (pintype "input"))
      (node (ref "IC1") (pin "14") (pinfunction "CS2~{}_14") (pintype "input"))
      (node (ref "IC1") (pin "25") (pinfunction "AS~{}_25") (pintype "input"))
      (node (ref "IC11") (pin "10") (pinfunction "I1_10") (pintype "input"))
      (node (ref "IC11") (pin "11") (pinfunction "I2_11") (pintype "input"))
      (node (ref "IC11") (pin "3") (pinfunction "I0_3") (pintype "input"))
      (node (ref "IC11") (pin "4") (pinfunction "I1_4") (pintype "input"))
      (node (ref "IC11") (pin "5") (pinfunction "I2_5") (pintype "input"))
      (node (ref "IC11") (pin "9") (pinfunction "I0_9") (pintype "input"))
      (node (ref "IC5") (pin "5") (pinfunction "G2B_5") (pintype "input"))
      (node (ref "IC7") (pin "10") (pinfunction "I1_10") (pintype "input"))
      (node (ref "IC7") (pin "9") (pinfunction "I0_9") (pintype "input"))
      (node (ref "IN") (pin "3") (pinfunction "S_3") (pintype "passive"))
      (node (ref "IO-ADDR-HL") (pin "1") (pinfunction "1_1") (pintype "passive"))
      (node (ref "J1") (pin "5") (pinfunction "5_5") (pintype "passive"))
      (node (ref "LO") (pin "5") (pinfunction "L-SI_5") (pintype "input"))
      (node (ref "LO") (pin "7") (pinfunction "GND_7") (pintype "power_in"))
      (node (ref "LO") (pin "8") (pinfunction "BI_8") (pintype "input"))
      (node (ref "OUT") (pin "K") (pinfunction "C_K") (pintype "passive"))
      (node (ref "PWR") (pin "K") (pinfunction "C_K") (pintype "passive"))
      (node (ref "S0") (pin "3") (pinfunction "S_3") (pintype "passive"))
      (node (ref "S1") (pin "3") (pinfunction "S_3") (pintype "passive"))
      (node (ref "S2") (pin "3") (pinfunction "S_3") (pintype "passive"))
      (node (ref "S3") (pin "3") (pinfunction "S_3") (pintype "passive"))
      (node (ref "S4") (pin "3") (pinfunction "S_3") (pintype "passive"))
      (node (ref "S5") (pin "3") (pinfunction "S_3") (pintype "passive"))
      (node (ref "S6") (pin "3") (pinfunction "S_3") (pintype "passive"))
      (node (ref "S7") (pin "3") (pinfunction "S_3") (pintype "passive"))
      (node (ref "TM1") (pin "3") (pinfunction "E_3") (pintype "passive"))
      (node (ref "X1") (pin "A1") (pinfunction "B_A1") (pintype "passive"))
      (node (ref "X1") (pin "A32") (pinfunction "B_A32") (pintype "passive"))
      (node (ref "X1") (pin "B1") (pinfunction "B_B1") (pintype "passive"))
      (node (ref "X1") (pin "B32") (pinfunction "B_B32") (pintype "passive"))
      (node (ref "X1") (pin "C1") (pinfunction "B_C1") (pintype "passive"))
      (node (ref "X1") (pin "C32") (pinfunction "B_C32") (pintype "passive"))
      (node (ref "X2") (pin "1") (pinfunction "VSS_1") (pintype "power_in"))
      (node (ref "X2") (pin "16") (pinfunction "K_16") (pintype "input"))
      (node (ref "X2") (pin "5") (pinfunction "RW_5") (pintype "input"))
      (node (ref "Y1") (pin "4") (pinfunction "GND_4") (pintype "power_in"))
    )
    (net (code "83") (name "ICLK") (class "Default")
      (node (ref "IC1") (pin "15") (pinfunction "BAUDOUT~{}_15") (pintype "output"))
      (node (ref "IC1") (pin "9") (pinfunction "RCLK_9") (pintype "input"))
    )
    (net (code "84") (name "IN") (class "Default")
      (node (ref "INPUT") (pin "1") (pinfunction "1_1") (pintype "passive"))
      (node (ref "X1") (pin "C26") (pinfunction "B_C26") (pintype "passive"))
    )
    (net (code "85") (name "IO-ADDR0") (class "Default")
      (node (ref "IC5") (pin "1") (pinfunction "A_1") (pintype "input"))
      (node (ref "X1") (pin "C7") (pinfunction "B_C7") (pintype "passive"))
    )
    (net (code "86") (name "IO-ADDR1") (class "Default")
      (node (ref "IC5") (pin "2") (pinfunction "B_2") (pintype "input"))
      (node (ref "X1") (pin "C8") (pinfunction "B_C8") (pintype "passive"))
    )
    (net (code "87") (name "IO-ADDR2") (class "Default")
      (node (ref "IC5") (pin "3") (pinfunction "C_3") (pintype "input"))
      (node (ref "X1") (pin "C9") (pinfunction "B_C9") (pintype "passive"))
    )
    (net (code "88") (name "IO-ADDR3") (class "Default")
      (node (ref "IO-ADDR-HL") (pin "2") (pinfunction "2_2") (pintype "passive"))
      (node (ref "IO-ADDR-HL") (pin "5") (pinfunction "5_5") (pintype "passive"))
      (node (ref "X1") (pin "C10") (pinfunction "B_C10") (pintype "passive"))
    )
    (net (code "89") (name "IO-RD") (class "Default")
      (node (ref "IC1") (pin "22") (pinfunction "IOR_22") (pintype "input"))
      (node (ref "IC6") (pin "3") (pinfunction "I0_3") (pintype "input"))
      (node (ref "IC8") (pin "2") (pinfunction "O_2") (pintype "open_collector"))
      (node (ref "RN2") (pin "7") (pinfunction "1_7") (pintype "passive"))
    )
    (net (code "90") (name "IO-SELDATA") (class "Default")
      (node (ref "IC1") (pin "12") (pinfunction "CS0_12") (pintype "input"))
      (node (ref "IC11") (pin "2") (pinfunction "I1_2") (pintype "input"))
      (node (ref "IC6") (pin "2") (pinfunction "I1_2") (pintype "input"))
      (node (ref "IC6") (pin "4") (pinfunction "I1_4") (pintype "input"))
      (node (ref "IC6") (pin "9") (pinfunction "I0_9") (pintype "input"))
      (node (ref "IC8") (pin "10") (pinfunction "O_10") (pintype "open_collector"))
      (node (ref "RN2") (pin "3") (pinfunction "1_3") (pintype "passive"))
    )
    (net (code "91") (name "IO-WR") (class "Default")
      (node (ref "IC1") (pin "19") (pinfunction "IOW_19") (pintype "input"))
      (node (ref "IC11") (pin "1") (pinfunction "I0_1") (pintype "input"))
      (node (ref "IC6") (pin "1") (pinfunction "I0_1") (pintype "input"))
      (node (ref "IC6") (pin "11") (pinfunction "I2_11") (pintype "input"))
      (node (ref "IC7") (pin "5") (pinfunction "I1_5") (pintype "input"))
      (node (ref "IC8") (pin "4") (pinfunction "O_4") (pintype "open_collector"))
      (node (ref "RN2") (pin "6") (pinfunction "1_6") (pintype "passive"))
    )
    (net (code "92") (name "LCD-ENABLE") (class "Default")
      (node (ref "IC10") (pin "5") (pinfunction "Q2_5") (pintype "output"))
      (node (ref "IC6") (pin "10") (pinfunction "I1_10") (pintype "input"))
    )
    (net (code "93") (name "LCD-REGISTER") (class "Default")
      (node (ref "IC10") (pin "6") (pinfunction "Q3_6") (pintype "output"))
      (node (ref "X2") (pin "4") (pinfunction "RS_4") (pintype "input"))
    )
    (net (code "94") (name "Net-(0-PadA)") (class "Default")
      (node (ref "0") (pin "A") (pinfunction "A_A") (pintype "passive"))
      (node (ref "R3") (pin "1") (pinfunction "1_1") (pintype "passive"))
    )
    (net (code "95") (name "Net-(1-PadA)") (class "Default")
      (node (ref "1") (pin "A") (pinfunction "A_A") (pintype "passive"))
      (node (ref "R4") (pin "1") (pinfunction "1_1") (pintype "passive"))
    )
    (net (code "96") (name "Net-(2-PadA)") (class "Default")
      (node (ref "2") (pin "A") (pinfunction "A_A") (pintype "passive"))
      (node (ref "R5") (pin "1") (pinfunction "1_1") (pintype "passive"))
    )
    (net (code "97") (name "Net-(3-PadA)") (class "Default")
      (node (ref "3") (pin "A") (pinfunction "A_A") (pintype "passive"))
      (node (ref "R6") (pin "1") (pinfunction "1_1") (pintype "passive"))
    )
    (net (code "98") (name "Net-(4-PadA)") (class "Default")
      (node (ref "4") (pin "A") (pinfunction "A_A") (pintype "passive"))
      (node (ref "R7") (pin "1") (pinfunction "1_1") (pintype "passive"))
    )
    (net (code "99") (name "Net-(5-PadA)") (class "Default")
      (node (ref "5") (pin "A") (pinfunction "A_A") (pintype "passive"))
      (node (ref "R8") (pin "1") (pinfunction "1_1") (pintype "passive"))
    )
    (net (code "100") (name "Net-(6-PadA)") (class "Default")
      (node (ref "6") (pin "A") (pinfunction "A_A") (pintype "passive"))
      (node (ref "R9") (pin "1") (pinfunction "1_1") (pintype "passive"))
    )
    (net (code "101") (name "Net-(7-PadA)") (class "Default")
      (node (ref "7") (pin "A") (pinfunction "A_A") (pintype "passive"))
      (node (ref "R10") (pin "1") (pinfunction "1_1") (pintype "passive"))
    )
    (net (code "102") (name "Net-(HIA-D0)") (class "Default")
      (node (ref "HI") (pin "3") (pinfunction "D0_3") (pintype "input"))
      (node (ref "IC9") (pin "12") (pinfunction "Q5_12") (pintype "output"))
    )
    (net (code "103") (name "Net-(HIA-D1)") (class "Default")
      (node (ref "HI") (pin "2") (pinfunction "D1_2") (pintype "input"))
      (node (ref "IC9") (pin "15") (pinfunction "Q6_15") (pintype "output"))
    )
    (net (code "104") (name "Net-(HIA-D2)") (class "Default")
      (node (ref "HI") (pin "13") (pinfunction "D2_13") (pintype "input"))
      (node (ref "IC9") (pin "16") (pinfunction "Q7_16") (pintype "output"))
    )
    (net (code "105") (name "Net-(HIA-D3)") (class "Default")
      (node (ref "HI") (pin "12") (pinfunction "D3_12") (pintype "input"))
      (node (ref "IC9") (pin "19") (pinfunction "Q8_19") (pintype "output"))
    )
    (net (code "106") (name "Net-(IC1A-INT)") (class "Default")
      (node (ref "IC1") (pin "30") (pinfunction "INT_30") (pintype "output"))
      (node (ref "INT") (pin "1") (pinfunction "1_1") (pintype "passive"))
    )
    (net (code "107") (name "Net-(IC1A-TX)") (class "Default")
      (node (ref "IC1") (pin "11") (pinfunction "TX_11") (pintype "output"))
      (node (ref "IC2") (pin "11") (pinfunction "T1IN_11") (pintype "input"))
    )
    (net (code "108") (name "Net-(IC1A-XTAL1)") (class "Default")
      (node (ref "IC1") (pin "16") (pinfunction "XTAL1_16") (pintype "input"))
      (node (ref "Y1") (pin "5") (pinfunction "OUTPUT_5") (pintype "output"))
    )
    (net (code "109") (name "Net-(IC2A-C1+)") (class "Default")
      (node (ref "C1") (pin "+") (pinfunction "+_+") (pintype "passive"))
      (node (ref "IC2") (pin "1") (pinfunction "C1+_1") (pintype "bidirectional"))
    )
    (net (code "110") (name "Net-(IC2A-C1-)") (class "Default")
      (node (ref "C1") (pin "-") (pinfunction "-_-") (pintype "passive"))
      (node (ref "IC2") (pin "3") (pinfunction "C1-_3") (pintype "bidirectional"))
    )
    (net (code "111") (name "Net-(IC2A-C2+)") (class "Default")
      (node (ref "C2") (pin "+") (pinfunction "+_+") (pintype "passive"))
      (node (ref "IC2") (pin "4") (pinfunction "C2+_4") (pintype "bidirectional"))
    )
    (net (code "112") (name "Net-(IC2A-C2-)") (class "Default")
      (node (ref "C2") (pin "-") (pinfunction "-_-") (pintype "passive"))
      (node (ref "IC2") (pin "5") (pinfunction "C2-_5") (pintype "bidirectional"))
    )
    (net (code "113") (name "Net-(IC2A-V+)") (class "Default")
      (node (ref "C3") (pin "+") (pinfunction "+_+") (pintype "passive"))
      (node (ref "IC2") (pin "2") (pinfunction "V+_2") (pintype "bidirectional"))
    )
    (net (code "114") (name "Net-(IC2A-V-)") (class "Default")
      (node (ref "C4") (pin "-") (pinfunction "-_-") (pintype "passive"))
      (node (ref "IC2") (pin "6") (pinfunction "V-_6") (pintype "bidirectional"))
    )
    (net (code "115") (name "Net-(IC3A-A1)") (class "Default")
      (node (ref "IC3") (pin "2") (pinfunction "A1_2") (pintype "input"))
      (node (ref "S0") (pin "2") (pinfunction "P_2") (pintype "passive"))
    )
    (net (code "116") (name "Net-(IC3A-A2)") (class "Default")
      (node (ref "IC3") (pin "4") (pinfunction "A2_4") (pintype "input"))
      (node (ref "S1") (pin "2") (pinfunction "P_2") (pintype "passive"))
    )
    (net (code "117") (name "Net-(IC3A-A3)") (class "Default")
      (node (ref "IC3") (pin "6") (pinfunction "A3_6") (pintype "input"))
      (node (ref "S2") (pin "2") (pinfunction "P_2") (pintype "passive"))
    )
    (net (code "118") (name "Net-(IC3A-A4)") (class "Default")
      (node (ref "IC3") (pin "8") (pinfunction "A4_8") (pintype "input"))
      (node (ref "S3") (pin "2") (pinfunction "P_2") (pintype "passive"))
    )
    (net (code "119") (name "Net-(IC3A-G)") (class "Default")
      (node (ref "IC3") (pin "1") (pinfunction "G_1") (pintype "input"))
      (node (ref "IC3") (pin "19") (pinfunction "G_19") (pintype "input"))
      (node (ref "IC6") (pin "6") (pinfunction "O_6") (pintype "output"))
    )
    (net (code "120") (name "Net-(IC3B-A1)") (class "Default")
      (node (ref "IC3") (pin "11") (pinfunction "A1_11") (pintype "input"))
      (node (ref "S4") (pin "2") (pinfunction "P_2") (pintype "passive"))
    )
    (net (code "121") (name "Net-(IC3B-A2)") (class "Default")
      (node (ref "IC3") (pin "13") (pinfunction "A2_13") (pintype "input"))
      (node (ref "S5") (pin "2") (pinfunction "P_2") (pintype "passive"))
    )
    (net (code "122") (name "Net-(IC3B-A3)") (class "Default")
      (node (ref "IC3") (pin "15") (pinfunction "A3_15") (pintype "input"))
      (node (ref "S6") (pin "2") (pinfunction "P_2") (pintype "passive"))
    )
    (net (code "123") (name "Net-(IC3B-A4)") (class "Default")
      (node (ref "IC3") (pin "17") (pinfunction "A4_17") (pintype "input"))
      (node (ref "S7") (pin "2") (pinfunction "P_2") (pintype "passive"))
    )
    (net (code "124") (name "Net-(IC4A-CLK)") (class "Default")
      (node (ref "IC4") (pin "11") (pinfunction "CLK_11") (pintype "input"))
      (node (ref "IC6") (pin "12") (pinfunction "O_12") (pintype "output"))
    )
    (net (code "125") (name "Net-(IC4A-Q1)") (class "Default")
      (node (ref "IC4") (pin "2") (pinfunction "Q1_2") (pintype "output"))
      (node (ref "R3") (pin "2") (pinfunction "2_2") (pintype "passive"))
    )
    (net (code "126") (name "Net-(IC4A-Q2)") (class "Default")
      (node (ref "IC4") (pin "5") (pinfunction "Q2_5") (pintype "output"))
      (node (ref "R4") (pin "2") (pinfunction "2_2") (pintype "passive"))
    )
    (net (code "127") (name "Net-(IC4A-Q3)") (class "Default")
      (node (ref "IC4") (pin "6") (pinfunction "Q3_6") (pintype "output"))
      (node (ref "R5") (pin "2") (pinfunction "2_2") (pintype "passive"))
    )
    (net (code "128") (name "Net-(IC4A-Q4)") (class "Default")
      (node (ref "IC4") (pin "9") (pinfunction "Q4_9") (pintype "output"))
      (node (ref "R6") (pin "2") (pinfunction "2_2") (pintype "passive"))
    )
    (net (code "129") (name "Net-(IC4A-Q5)") (class "Default")
      (node (ref "IC4") (pin "12") (pinfunction "Q5_12") (pintype "output"))
      (node (ref "R7") (pin "2") (pinfunction "2_2") (pintype "passive"))
    )
    (net (code "130") (name "Net-(IC4A-Q6)") (class "Default")
      (node (ref "IC4") (pin "15") (pinfunction "Q6_15") (pintype "output"))
      (node (ref "R8") (pin "2") (pinfunction "2_2") (pintype "passive"))
    )
    (net (code "131") (name "Net-(IC4A-Q7)") (class "Default")
      (node (ref "IC4") (pin "16") (pinfunction "Q7_16") (pintype "output"))
      (node (ref "R9") (pin "2") (pinfunction "2_2") (pintype "passive"))
    )
    (net (code "132") (name "Net-(IC4A-Q8)") (class "Default")
      (node (ref "IC4") (pin "19") (pinfunction "Q8_19") (pintype "output"))
      (node (ref "R10") (pin "2") (pinfunction "2_2") (pintype "passive"))
    )
    (net (code "133") (name "Net-(IC5A-G1)") (class "Default")
      (node (ref "IC5") (pin "6") (pinfunction "G1_6") (pintype "input"))
      (node (ref "IO-ADDR-HL") (pin "4") (pinfunction "4_4") (pintype "passive"))
    )
    (net (code "134") (name "Net-(IC5A-G2A)") (class "Default")
      (node (ref "IC5") (pin "4") (pinfunction "G2A_4") (pintype "input"))
      (node (ref "IO-ADDR-HL") (pin "3") (pinfunction "3_3") (pintype "passive"))
    )
    (net (code "135") (name "Net-(IC6C-O)") (class "Default")
      (node (ref "IC6") (pin "8") (pinfunction "O_8") (pintype "output"))
      (node (ref "IC7") (pin "1") (pinfunction "I0_1") (pintype "input"))
      (node (ref "IC7") (pin "2") (pinfunction "I1_2") (pintype "input"))
    )
    (net (code "136") (name "Net-(IC7A-O)") (class "Default")
      (node (ref "IC7") (pin "3") (pinfunction "O_3") (pintype "output"))
      (node (ref "X2") (pin "6") (pinfunction "E_6") (pintype "input"))
    )
    (net (code "137") (name "Net-(IC7B-I0)") (class "Default")
      (node (ref "IC7") (pin "11") (pinfunction "O_11") (pintype "output"))
      (node (ref "IC7") (pin "4") (pinfunction "I0_4") (pintype "input"))
    )
    (net (code "138") (name "Net-(IC8F-I)") (class "Default")
      (node (ref "IC8") (pin "13") (pinfunction "I_13") (pintype "input"))
      (node (ref "INT") (pin "2") (pinfunction "2_2") (pintype "passive"))
    )
    (net (code "139") (name "Net-(IC9A-Q1)") (class "Default")
      (node (ref "IC9") (pin "2") (pinfunction "Q1_2") (pintype "output"))
      (node (ref "LO") (pin "3") (pinfunction "D0_3") (pintype "input"))
    )
    (net (code "140") (name "Net-(IC9A-Q2)") (class "Default")
      (node (ref "IC9") (pin "5") (pinfunction "Q2_5") (pintype "output"))
      (node (ref "LO") (pin "2") (pinfunction "D1_2") (pintype "input"))
    )
    (net (code "141") (name "Net-(IC9A-Q3)") (class "Default")
      (node (ref "IC9") (pin "6") (pinfunction "Q3_6") (pintype "output"))
      (node (ref "LO") (pin "13") (pinfunction "D2_13") (pintype "input"))
    )
    (net (code "142") (name "Net-(IC9A-Q4)") (class "Default")
      (node (ref "IC9") (pin "9") (pinfunction "Q4_9") (pintype "output"))
      (node (ref "LO") (pin "12") (pinfunction "D3_12") (pintype "input"))
    )
    (net (code "143") (name "Net-(IC10A-CLK)") (class "Default")
      (node (ref "IC10") (pin "11") (pinfunction "CLK_11") (pintype "input"))
      (node (ref "IC7") (pin "6") (pinfunction "O_6") (pintype "output"))
    )
    (net (code "144") (name "Net-(IC11A-O)") (class "Default")
      (node (ref "IC11") (pin "12") (pinfunction "O_12") (pintype "output"))
      (node (ref "IC9") (pin "11") (pinfunction "CLK_11") (pintype "input"))
    )
    (net (code "145") (name "Net-(IN-P)") (class "Default")
      (node (ref "IN") (pin "2") (pinfunction "P_2") (pintype "passive"))
      (node (ref "INPUT") (pin "2") (pinfunction "2_2") (pintype "passive"))
    )
    (net (code "146") (name "Net-(J1-Pad2)") (class "Default")
      (node (ref "J1") (pin "2") (pinfunction "2_2") (pintype "passive"))
      (node (ref "JP1") (pin "4") (pinfunction "4_4") (pintype "passive"))
    )
    (net (code "147") (name "Net-(J1-Pad3)") (class "Default")
      (node (ref "J1") (pin "3") (pinfunction "3_3") (pintype "passive"))
      (node (ref "JP1") (pin "3") (pinfunction "3_3") (pintype "passive"))
    )
    (net (code "148") (name "Net-(OUT-PadA)") (class "Default")
      (node (ref "OUT") (pin "A") (pinfunction "A_A") (pintype "passive"))
      (node (ref "R1") (pin "1") (pinfunction "1_1") (pintype "passive"))
    )
    (net (code "149") (name "Net-(PWR-PadA)") (class "Default")
      (node (ref "PWR") (pin "A") (pinfunction "A_A") (pintype "passive"))
      (node (ref "R2") (pin "1") (pinfunction "1_1") (pintype "passive"))
    )
    (net (code "150") (name "Net-(TM1-S)") (class "Default")
      (node (ref "TM1") (pin "2") (pinfunction "S_2") (pintype "passive"))
      (node (ref "X2") (pin "3") (pinfunction "VO_3") (pintype "input"))
    )
    (net (code "151") (name "OUT") (class "Default")
      (node (ref "R1") (pin "2") (pinfunction "2_2") (pintype "passive"))
      (node (ref "X1") (pin "C27") (pinfunction "B_C27") (pintype "passive"))
    )
    (net (code "152") (name "REG-LD-ID0") (class "Default")
      (node (ref "X1") (pin "B13") (pinfunction "B_B13") (pintype "passive"))
    )
    (net (code "153") (name "REG-LD-ID1") (class "Default")
      (node (ref "X1") (pin "B14") (pinfunction "B_B14") (pintype "passive"))
    )
    (net (code "154") (name "REG-LD-ID2") (class "Default")
      (node (ref "X1") (pin "B15") (pinfunction "B_B15") (pintype "passive"))
    )
    (net (code "155") (name "REG-LD-ID3") (class "Default")
      (node (ref "X1") (pin "B16") (pinfunction "B_B16") (pintype "passive"))
    )
    (net (code "156") (name "REG-RD-ID0") (class "Default")
      (node (ref "X1") (pin "B9") (pinfunction "B_B9") (pintype "passive"))
    )
    (net (code "157") (name "REG-RD-ID1") (class "Default")
      (node (ref "X1") (pin "B10") (pinfunction "B_B10") (pintype "passive"))
    )
    (net (code "158") (name "REG-RD-ID2") (class "Default")
      (node (ref "X1") (pin "B11") (pinfunction "B_B11") (pintype "passive"))
    )
    (net (code "159") (name "REG-RD-ID3") (class "Default")
      (node (ref "X1") (pin "B12") (pinfunction "B_B12") (pintype "passive"))
    )
    (net (code "160") (name "RESET") (class "Default")
      (node (ref "IC1") (pin "35") (pinfunction "RESET_35") (pintype "input"))
      (node (ref "IC8") (pin "6") (pinfunction "O_6") (pintype "open_collector"))
      (node (ref "IC8") (pin "9") (pinfunction "I_9") (pintype "input"))
      (node (ref "RN2") (pin "5") (pinfunction "1_5") (pintype "passive"))
    )
    (net (code "161") (name "RX") (class "Default")
      (node (ref "IC1") (pin "10") (pinfunction "RX_10") (pintype "input"))
      (node (ref "IC2") (pin "12") (pinfunction "R1OUT_12") (pintype "output"))
    )
    (net (code "162") (name "RX-IN") (class "Default")
      (node (ref "IC2") (pin "13") (pinfunction "R1IN_13") (pintype "input"))
      (node (ref "JP1") (pin "1") (pinfunction "1_1") (pintype "passive"))
      (node (ref "JP1") (pin "6") (pinfunction "6_6") (pintype "passive"))
    )
    (net (code "163") (name "SWITCH-LED") (class "Default")
      (node (ref "IC10") (pin "2") (pinfunction "Q1_2") (pintype "output"))
      (node (ref "IC6") (pin "13") (pinfunction "I2_13") (pintype "input"))
      (node (ref "IC6") (pin "5") (pinfunction "I2_5") (pintype "input"))
    )
    (net (code "164") (name "TIL311") (class "Default")
      (node (ref "IC10") (pin "19") (pinfunction "Q8_19") (pintype "output"))
      (node (ref "IC11") (pin "13") (pinfunction "I2_13") (pintype "input"))
    )
    (net (code "165") (name "TX-OUT") (class "Default")
      (node (ref "IC2") (pin "14") (pinfunction "T1OUT_14") (pintype "output"))
      (node (ref "JP1") (pin "2") (pinfunction "2_2") (pintype "passive"))
      (node (ref "JP1") (pin "5") (pinfunction "5_5") (pintype "passive"))
    )
    (net (code "166") (name "UART-A0") (class "Default")
      (node (ref "IC1") (pin "28") (pinfunction "A0_28") (pintype "input"))
      (node (ref "IC10") (pin "9") (pinfunction "Q4_9") (pintype "output"))
    )
    (net (code "167") (name "UART-A1") (class "Default")
      (node (ref "IC1") (pin "27") (pinfunction "A1_27") (pintype "input"))
      (node (ref "IC10") (pin "12") (pinfunction "Q5_12") (pintype "output"))
    )
    (net (code "168") (name "UART-A2") (class "Default")
      (node (ref "IC1") (pin "26") (pinfunction "A2_26") (pintype "input"))
      (node (ref "IC10") (pin "15") (pinfunction "Q6_15") (pintype "output"))
    )
    (net (code "169") (name "UART-CS") (class "Default")
      (node (ref "IC1") (pin "13") (pinfunction "CS1_13") (pintype "input"))
      (node (ref "IC10") (pin "16") (pinfunction "Q7_16") (pintype "output"))
    )
    (net (code "170") (name "VCC") (class "Default")
      (node (ref "C10") (pin "1") (pinfunction "1_1") (pintype "passive"))
      (node (ref "C11") (pin "1") (pinfunction "1_1") (pintype "passive"))
      (node (ref "C12") (pin "1") (pinfunction "1_1") (pintype "passive"))
      (node (ref "C13") (pin "1") (pinfunction "1_1") (pintype "passive"))
      (node (ref "C14") (pin "1") (pinfunction "1_1") (pintype "passive"))
      (node (ref "C15") (pin "1") (pinfunction "1_1") (pintype "passive"))
      (node (ref "C16") (pin "1") (pinfunction "1_1") (pintype "passive"))
      (node (ref "C17") (pin "1") (pinfunction "1_1") (pintype "passive"))
      (node (ref "C3") (pin "-") (pinfunction "-_-") (pintype "passive"))
      (node (ref "C5") (pin "1") (pinfunction "1_1") (pintype "passive"))
      (node (ref "C6") (pin "1") (pinfunction "1_1") (pintype "passive"))
      (node (ref "C7") (pin "1") (pinfunction "1_1") (pintype "passive"))
      (node (ref "C8") (pin "1") (pinfunction "1_1") (pintype "passive"))
      (node (ref "C9") (pin "1") (pinfunction "1_1") (pintype "passive"))
      (node (ref "HI") (pin "1") (pinfunction "LEDSUP_1") (pintype "input"))
      (node (ref "HI") (pin "14") (pinfunction "VCC_14") (pintype "power_in"))
      (node (ref "IC1") (pin "18") (pinfunction "IOW~{}_18") (pintype "input"))
      (node (ref "IC1") (pin "21") (pinfunction "IOR~{}_21") (pintype "input"))
      (node (ref "IC1") (pin "36") (pinfunction "CTS~{}_36") (pintype "input"))
      (node (ref "IC1") (pin "37") (pinfunction "DSR~{}_37") (pintype "input"))
      (node (ref "IC1") (pin "38") (pinfunction "CD~{}_38") (pintype "input"))
      (node (ref "IC1") (pin "39") (pinfunction "RI~{}_39") (pintype "input"))
      (node (ref "IN") (pin "1") (pinfunction "O_1") (pintype "passive"))
      (node (ref "IO-ADDR-HL") (pin "6") (pinfunction "6_6") (pintype "passive"))
      (node (ref "LO") (pin "1") (pinfunction "LEDSUP_1") (pintype "input"))
      (node (ref "LO") (pin "14") (pinfunction "VCC_14") (pintype "power_in"))
      (node (ref "R2") (pin "2") (pinfunction "2_2") (pintype "passive"))
      (node (ref "RN2") (pin "1") (pinfunction "1_1") (pintype "passive"))
      (node (ref "S0") (pin "1") (pinfunction "O_1") (pintype "passive"))
      (node (ref "S1") (pin "1") (pinfunction "O_1") (pintype "passive"))
      (node (ref "S2") (pin "1") (pinfunction "O_1") (pintype "passive"))
      (node (ref "S3") (pin "1") (pinfunction "O_1") (pintype "passive"))
      (node (ref "S4") (pin "1") (pinfunction "O_1") (pintype "passive"))
      (node (ref "S5") (pin "1") (pinfunction "O_1") (pintype "passive"))
      (node (ref "S6") (pin "1") (pinfunction "O_1") (pintype "passive"))
      (node (ref "S7") (pin "1") (pinfunction "O_1") (pintype "passive"))
      (node (ref "TM1") (pin "1") (pinfunction "A_1") (pintype "passive"))
      (node (ref "X1") (pin "A2") (pinfunction "B_A2") (pintype "passive"))
      (node (ref "X1") (pin "A31") (pinfunction "B_A31") (pintype "passive"))
      (node (ref "X1") (pin "B2") (pinfunction "B_B2") (pintype "passive"))
      (node (ref "X1") (pin "B31") (pinfunction "B_B31") (pintype "passive"))
      (node (ref "X1") (pin "C2") (pinfunction "B_C2") (pintype "passive"))
      (node (ref "X1") (pin "C31") (pinfunction "B_C31") (pintype "passive"))
      (node (ref "X2") (pin "15") (pinfunction "A_15") (pintype "input"))
      (node (ref "X2") (pin "2") (pinfunction "VDD_2") (pintype "power_in"))
      (node (ref "Y1") (pin "8") (pinfunction "+5VDC_8") (pintype "input"))
    )
    (net (code "171") (name "unconnected-(HIA-DP-L-Pad4)") (class "Default")
      (node (ref "HI") (pin "4") (pinfunction "DP-L_4") (pintype "input"))
    )
    (net (code "172") (name "unconnected-(HIA-DP-R-Pad10)") (class "Default")
      (node (ref "HI") (pin "10") (pinfunction "DP-R_10") (pintype "input"))
    )
    (net (code "173") (name "unconnected-(IC1A-DDIS~{}-Pad23)") (class "Default")
      (node (ref "IC1") (pin "23") (pinfunction "DDIS~{}_23") (pintype "output"))
    )
    (net (code "174") (name "unconnected-(IC1A-DTR~{}-Pad33)") (class "Default")
      (node (ref "IC1") (pin "33") (pinfunction "DTR~{}_33") (pintype "output"))
    )
    (net (code "175") (name "unconnected-(IC1A-OP1~{}-Pad34)") (class "Default")
      (node (ref "IC1") (pin "34") (pinfunction "OP1~{}_34") (pintype "output"))
    )
    (net (code "176") (name "unconnected-(IC1A-OP2~{}-Pad31)") (class "Default")
      (node (ref "IC1") (pin "31") (pinfunction "OP2~{}_31") (pintype "output"))
    )
    (net (code "177") (name "unconnected-(IC1A-RTS~{}-Pad32)") (class "Default")
      (node (ref "IC1") (pin "32") (pinfunction "RTS~{}_32") (pintype "output"))
    )
    (net (code "178") (name "unconnected-(IC1A-RXRDY~{}-Pad29)") (class "Default")
      (node (ref "IC1") (pin "29") (pinfunction "RXRDY~{}_29") (pintype "output"))
    )
    (net (code "179") (name "unconnected-(IC1A-TXRDY~{}-Pad24)") (class "Default")
      (node (ref "IC1") (pin "24") (pinfunction "TXRDY~{}_24") (pintype "output"))
    )
    (net (code "180") (name "unconnected-(IC1A-XTAL2-Pad17)") (class "Default")
      (node (ref "IC1") (pin "17") (pinfunction "XTAL2_17") (pintype "input"))
    )
    (net (code "181") (name "unconnected-(IC2A-R2IN-Pad8)") (class "Default")
      (node (ref "IC2") (pin "8") (pinfunction "R2IN_8") (pintype "input"))
    )
    (net (code "182") (name "unconnected-(IC2A-R2OUT-Pad9)") (class "Default")
      (node (ref "IC2") (pin "9") (pinfunction "R2OUT_9") (pintype "output"))
    )
    (net (code "183") (name "unconnected-(IC2A-T2IN-Pad10)") (class "Default")
      (node (ref "IC2") (pin "10") (pinfunction "T2IN_10") (pintype "input"))
    )
    (net (code "184") (name "unconnected-(IC2A-T2OUT-Pad7)") (class "Default")
      (node (ref "IC2") (pin "7") (pinfunction "T2OUT_7") (pintype "output"))
    )
    (net (code "185") (name "unconnected-(IC7C-O-Pad8)") (class "Default")
      (node (ref "IC7") (pin "8") (pinfunction "O_8") (pintype "output"))
    )
    (net (code "186") (name "unconnected-(IC11B-O-Pad6)") (class "Default")
      (node (ref "IC11") (pin "6") (pinfunction "O_6") (pintype "output"))
    )
    (net (code "187") (name "unconnected-(IC11C-O-Pad8)") (class "Default")
      (node (ref "IC11") (pin "8") (pinfunction "O_8") (pintype "output"))
    )
    (net (code "188") (name "unconnected-(J1-Pad1)") (class "Default")
      (node (ref "J1") (pin "1") (pinfunction "1_1") (pintype "passive"))
    )
    (net (code "189") (name "unconnected-(J1-Pad4)") (class "Default")
      (node (ref "J1") (pin "4") (pinfunction "4_4") (pintype "passive"))
    )
    (net (code "190") (name "unconnected-(J1-Pad6)") (class "Default")
      (node (ref "J1") (pin "6") (pinfunction "6_6") (pintype "passive"))
    )
    (net (code "191") (name "unconnected-(J1-Pad7)") (class "Default")
      (node (ref "J1") (pin "7") (pinfunction "7_7") (pintype "passive"))
    )
    (net (code "192") (name "unconnected-(J1-Pad8)") (class "Default")
      (node (ref "J1") (pin "8") (pinfunction "8_8") (pintype "passive"))
    )
    (net (code "193") (name "unconnected-(J1-Pad9)") (class "Default")
      (node (ref "J1") (pin "9") (pinfunction "9_9") (pintype "passive"))
    )
    (net (code "194") (name "unconnected-(LOA-DP-L-Pad4)") (class "Default")
      (node (ref "LO") (pin "4") (pinfunction "DP-L_4") (pintype "input"))
    )
    (net (code "195") (name "unconnected-(LOA-DP-R-Pad10)") (class "Default")
      (node (ref "LO") (pin "10") (pinfunction "DP-R_10") (pintype "input"))
    )
  )
)
